# WallFollower-Circle.net
KiCad netlist of a schematic drawn in EAGLE
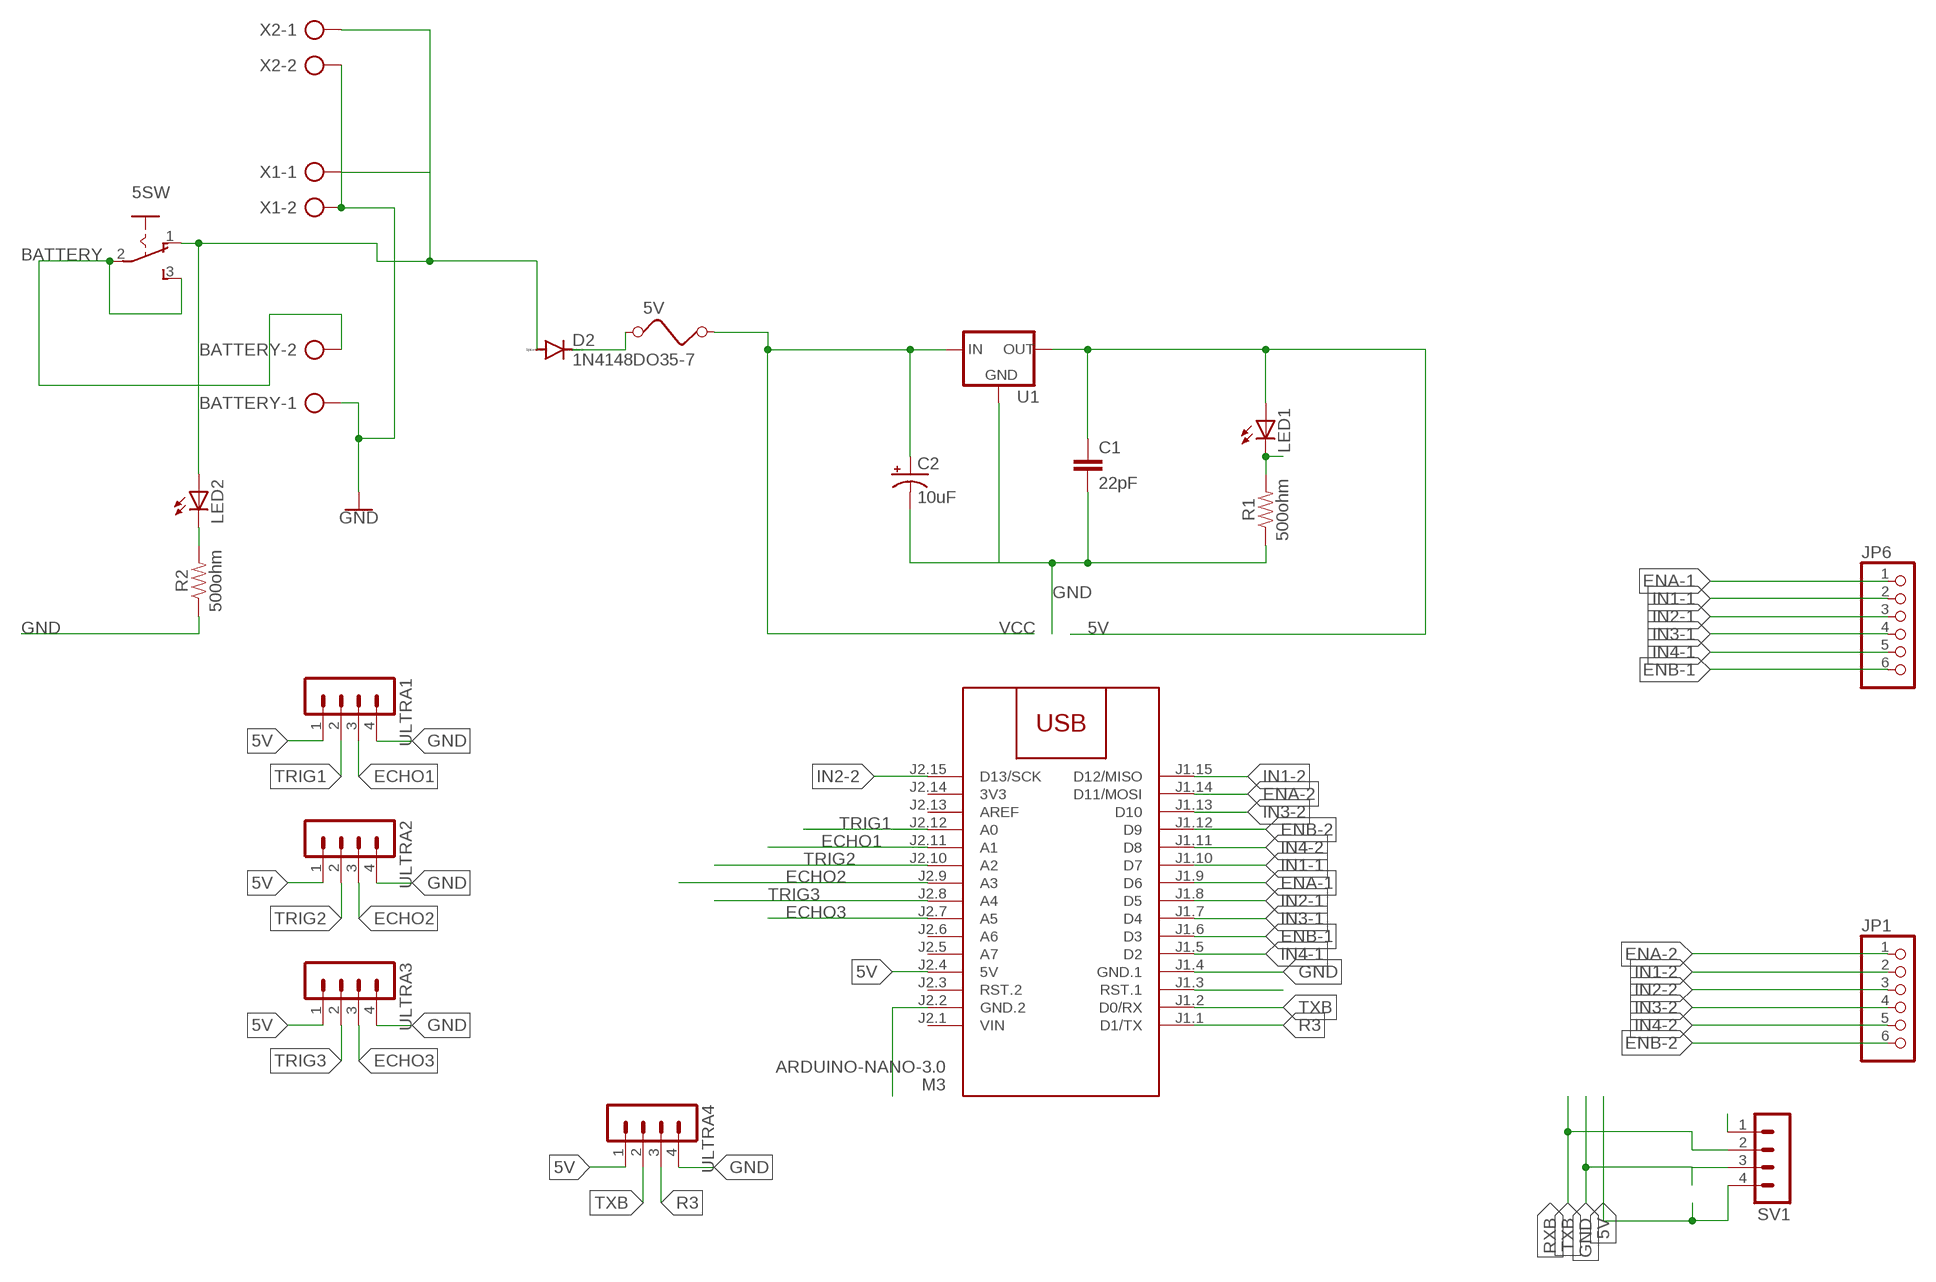
[diagram p0: schematic, sheet 1]

(export (version "E")
  (design (tool "Eeschema 10.0.6"))
  (components
    (comp (ref "5SW")
      (value "255SB")
      (footprint "eagle-import:255SB")
      (libsource (lib "eagle-import") (part "255SB"))
    )
    (comp (ref "5V")
      (value "FUSE")
      (footprint "eagle-import:FUSE")
      (libsource (lib "eagle-import") (part "FUSE"))
    )
    (comp (ref "BATTERY")
      (value "AK500/2-H")
      (footprint "eagle-import:AK500_2-H")
      (libsource (lib "eagle-import") (part "AK500/2-H"))
    )
    (comp (ref "C1")
      (value "22pF")
      (footprint "eagle-import:CAP-PTH-2.54")
      (libsource (lib "eagle-import") (part "22PF-PTH-2.54MM-200V-5%"))
    )
    (comp (ref "C2")
      (value "10uF")
      (footprint "eagle-import:CPOL-RADIAL-2.5MM-5MM")
      (libsource (lib "eagle-import") (part "10UF-POLAR-RADIAL-2.5MM-25V-20%"))
    )
    (comp (ref "D2")
      (value "1N4148DO35-7")
      (footprint "eagle-import:DO35-7")
      (libsource (lib "eagle-import") (part "1N4148DO35-7"))
    )
    (comp (ref "JP1")
      (value "PINHD-1X6")
      (footprint "eagle-import:1X06")
      (libsource (lib "eagle-import") (part "PINHD-1X6"))
    )
    (comp (ref "JP6")
      (value "PINHD-1X6")
      (footprint "eagle-import:1X06")
      (libsource (lib "eagle-import") (part "PINHD-1X6"))
    )
    (comp (ref "LED1")
      (value "LED3MM")
      (footprint "eagle-import:LED3MM")
      (libsource (lib "eagle-import") (part "LED3MM"))
    )
    (comp (ref "LED2")
      (value "LED3MM")
      (footprint "eagle-import:LED3MM")
      (libsource (lib "eagle-import") (part "LED3MM"))
    )
    (comp (ref "M3")
      (value "ARDUINO-NANO-3.0")
      (footprint "eagle-import:ARDUINO-NANO-3.0")
      (libsource (lib "eagle-import") (part "ARDUINO-NANO-3.0"))
    )
    (comp (ref "R1")
      (value "500ohm")
      (footprint "eagle-import:AXIAL-0.3")
      (libsource (lib "eagle-import") (part "10MOHM-HORIZ-1/4W-5%"))
    )
    (comp (ref "R2")
      (value "500ohm")
      (footprint "eagle-import:AXIAL-0.3")
      (libsource (lib "eagle-import") (part "10MOHM-HORIZ-1/4W-5%"))
    )
    (comp (ref "SV1")
      (value "MA04-1")
      (footprint "eagle-import:MA04-1")
      (libsource (lib "eagle-import") (part "MA04-1"))
    )
    (comp (ref "U1")
      (value "78XXS")
      (footprint "eagle-import:78XXS")
      (libsource (lib "eagle-import") (part "78XXS"))
    )
    (comp (ref "ULTRA1")
      (value "MA04-1")
      (footprint "eagle-import:MA04-1")
      (libsource (lib "eagle-import") (part "MA04-1"))
    )
    (comp (ref "ULTRA2")
      (value "MA04-1")
      (footprint "eagle-import:MA04-1")
      (libsource (lib "eagle-import") (part "MA04-1"))
    )
    (comp (ref "ULTRA3")
      (value "MA04-1")
      (footprint "eagle-import:MA04-1")
      (libsource (lib "eagle-import") (part "MA04-1"))
    )
    (comp (ref "ULTRA4")
      (value "MA04-1")
      (footprint "eagle-import:MA04-1")
      (libsource (lib "eagle-import") (part "MA04-1"))
    )
    (comp (ref "X1")
      (value "AK500/2-H")
      (footprint "eagle-import:AK500_2-H")
      (libsource (lib "eagle-import") (part "AK500/2-H"))
    )
    (comp (ref "X2")
      (value "AK500/2-H")
      (footprint "eagle-import:AK500_2-H")
      (libsource (lib "eagle-import") (part "AK500/2-H"))
    )
  )
  (nets
    (net (code "1") (name "/3V3") (class "Default")
      (node (ref "M3") (pin "J2.14") (pinfunction "3V3_J2.14") (pintype "power_in"))
    )
    (net (code "2") (name "/BATTERY") (class "Default")
      (node (ref "5SW") (pin "2") (pinfunction "P_2") (pintype "passive"))
      (node (ref "5SW") (pin "3") (pinfunction "S_3") (pintype "passive"))
      (node (ref "BATTERY") (pin "2") (pinfunction "KL_2") (pintype "passive"))
    )
    (net (code "3") (name "/VCC") (class "Default")
      (node (ref "5V") (pin "2") (pinfunction "2_2") (pintype "passive"))
      (node (ref "C2") (pin "1") (pinfunction "+_1") (pintype "passive"))
      (node (ref "U1") (pin "IN") (pinfunction "IN_IN") (pintype "input"))
    )
    (net (code "4") (name "/VIN") (class "Default")
      (node (ref "M3") (pin "J2.1") (pinfunction "VIN_J2.1") (pintype "power_in"))
    )
    (net (code "5") (name "5V") (class "Default")
      (node (ref "C1") (pin "1") (pinfunction "1_1") (pintype "passive"))
      (node (ref "LED1") (pin "A") (pinfunction "A_A") (pintype "passive"))
      (node (ref "M3") (pin "J2.4") (pinfunction "5V_J2.4") (pintype "power_in"))
      (node (ref "SV1") (pin "4") (pinfunction "4_4") (pintype "passive"))
      (node (ref "U1") (pin "OUT") (pinfunction "OUT_OUT") (pintype "passive"))
      (node (ref "ULTRA1") (pin "1") (pinfunction "1_1") (pintype "passive"))
      (node (ref "ULTRA2") (pin "1") (pinfunction "1_1") (pintype "passive"))
      (node (ref "ULTRA3") (pin "1") (pinfunction "1_1") (pintype "passive"))
      (node (ref "ULTRA4") (pin "1") (pinfunction "1_1") (pintype "passive"))
    )
    (net (code "6") (name "ECHO1") (class "Default")
      (node (ref "M3") (pin "J2.11") (pinfunction "A1_J2.11") (pintype "bidirectional"))
      (node (ref "ULTRA1") (pin "3") (pinfunction "3_3") (pintype "passive"))
    )
    (net (code "7") (name "ECHO2") (class "Default")
      (node (ref "M3") (pin "J2.9") (pinfunction "A3_J2.9") (pintype "bidirectional"))
      (node (ref "ULTRA2") (pin "3") (pinfunction "3_3") (pintype "passive"))
    )
    (net (code "8") (name "ECHO3") (class "Default")
      (node (ref "M3") (pin "J2.7") (pinfunction "A5_J2.7") (pintype "bidirectional"))
      (node (ref "ULTRA3") (pin "3") (pinfunction "3_3") (pintype "passive"))
    )
    (net (code "9") (name "ENA-1") (class "Default")
      (node (ref "JP6") (pin "1") (pinfunction "1_1") (pintype "passive"))
      (node (ref "M3") (pin "J1.9") (pinfunction "D6_J1.9") (pintype "bidirectional"))
    )
    (net (code "10") (name "ENA-2") (class "Default")
      (node (ref "JP1") (pin "1") (pinfunction "1_1") (pintype "passive"))
      (node (ref "M3") (pin "J1.14") (pinfunction "D11/MOSI_J1.14") (pintype "bidirectional"))
    )
    (net (code "11") (name "ENB-1") (class "Default")
      (node (ref "JP6") (pin "6") (pinfunction "6_6") (pintype "passive"))
      (node (ref "M3") (pin "J1.6") (pinfunction "D3_J1.6") (pintype "bidirectional"))
    )
    (net (code "12") (name "ENB-2") (class "Default")
      (node (ref "JP1") (pin "6") (pinfunction "6_6") (pintype "passive"))
      (node (ref "M3") (pin "J1.12") (pinfunction "D9_J1.12") (pintype "bidirectional"))
    )
    (net (code "13") (name "GND") (class "Default")
      (node (ref "BATTERY") (pin "1") (pinfunction "KL_1") (pintype "passive"))
      (node (ref "C1") (pin "2") (pinfunction "2_2") (pintype "passive"))
      (node (ref "C2") (pin "2") (pinfunction "-_2") (pintype "passive"))
      (node (ref "M3") (pin "J1.4") (pinfunction "GND.1_J1.4") (pintype "power_in"))
      (node (ref "M3") (pin "J2.2") (pinfunction "GND.2_J2.2") (pintype "power_in"))
      (node (ref "R1") (pin "P$1") (pinfunction "1_P$1") (pintype "passive"))
      (node (ref "R2") (pin "P$1") (pinfunction "1_P$1") (pintype "passive"))
      (node (ref "SV1") (pin "3") (pinfunction "3_3") (pintype "passive"))
      (node (ref "U1") (pin "GND") (pinfunction "GND_GND") (pintype "input"))
      (node (ref "ULTRA1") (pin "4") (pinfunction "4_4") (pintype "passive"))
      (node (ref "ULTRA2") (pin "4") (pinfunction "4_4") (pintype "passive"))
      (node (ref "ULTRA3") (pin "4") (pinfunction "4_4") (pintype "passive"))
      (node (ref "ULTRA4") (pin "4") (pinfunction "4_4") (pintype "passive"))
      (node (ref "X1") (pin "2") (pinfunction "KL_2") (pintype "passive"))
      (node (ref "X2") (pin "2") (pinfunction "KL_2") (pintype "passive"))
    )
    (net (code "14") (name "IN1-1") (class "Default")
      (node (ref "JP6") (pin "2") (pinfunction "2_2") (pintype "passive"))
      (node (ref "M3") (pin "J1.10") (pinfunction "D7_J1.10") (pintype "bidirectional"))
    )
    (net (code "15") (name "IN1-2") (class "Default")
      (node (ref "JP1") (pin "2") (pinfunction "2_2") (pintype "passive"))
      (node (ref "M3") (pin "J1.15") (pinfunction "D12/MISO_J1.15") (pintype "bidirectional"))
    )
    (net (code "16") (name "IN2-1") (class "Default")
      (node (ref "JP6") (pin "3") (pinfunction "3_3") (pintype "passive"))
      (node (ref "M3") (pin "J1.8") (pinfunction "D5_J1.8") (pintype "bidirectional"))
    )
    (net (code "17") (name "IN2-2") (class "Default")
      (node (ref "JP1") (pin "3") (pinfunction "3_3") (pintype "passive"))
      (node (ref "M3") (pin "J2.15") (pinfunction "D13/SCK_J2.15") (pintype "bidirectional"))
    )
    (net (code "18") (name "IN3-1") (class "Default")
      (node (ref "JP6") (pin "4") (pinfunction "4_4") (pintype "passive"))
      (node (ref "M3") (pin "J1.7") (pinfunction "D4_J1.7") (pintype "bidirectional"))
    )
    (net (code "19") (name "IN3-2") (class "Default")
      (node (ref "JP1") (pin "4") (pinfunction "4_4") (pintype "passive"))
      (node (ref "M3") (pin "J1.13") (pinfunction "D10_J1.13") (pintype "bidirectional"))
    )
    (net (code "20") (name "IN4-1") (class "Default")
      (node (ref "JP6") (pin "5") (pinfunction "5_5") (pintype "passive"))
      (node (ref "M3") (pin "J1.5") (pinfunction "D2_J1.5") (pintype "bidirectional"))
    )
    (net (code "21") (name "IN4-2") (class "Default")
      (node (ref "JP1") (pin "5") (pinfunction "5_5") (pintype "passive"))
      (node (ref "M3") (pin "J1.11") (pinfunction "D8_J1.11") (pintype "bidirectional"))
    )
    (net (code "22") (name "Net-(5SW-O)") (class "Default")
      (node (ref "5SW") (pin "1") (pinfunction "O_1") (pintype "passive"))
      (node (ref "D2") (pin "A") (pinfunction "A_A") (pintype "passive"))
      (node (ref "LED2") (pin "A") (pinfunction "A_A") (pintype "passive"))
      (node (ref "X1") (pin "1") (pinfunction "KL_1") (pintype "passive"))
      (node (ref "X2") (pin "1") (pinfunction "KL_1") (pintype "passive"))
    )
    (net (code "23") (name "Net-(5V-Pad1)") (class "Default")
      (node (ref "5V") (pin "1") (pinfunction "1_1") (pintype "passive"))
      (node (ref "D2") (pin "C") (pinfunction "C_C") (pintype "passive"))
    )
    (net (code "24") (name "Net-(LED1-C)") (class "Default")
      (node (ref "LED1") (pin "K") (pinfunction "C_K") (pintype "passive"))
      (node (ref "R1") (pin "P$2") (pinfunction "2_P$2") (pintype "passive"))
    )
    (net (code "25") (name "Net-(LED2-C)") (class "Default")
      (node (ref "LED2") (pin "K") (pinfunction "C_K") (pintype "passive"))
      (node (ref "R2") (pin "P$2") (pinfunction "2_P$2") (pintype "passive"))
    )
    (net (code "26") (name "R3") (class "Default")
      (node (ref "M3") (pin "J1.1") (pinfunction "D1/TX_J1.1") (pintype "bidirectional"))
      (node (ref "ULTRA4") (pin "3") (pinfunction "3_3") (pintype "passive"))
    )
    (net (code "27") (name "RXB") (class "Default")
      (node (ref "SV1") (pin "1") (pinfunction "1_1") (pintype "passive"))
    )
    (net (code "28") (name "TRIG1") (class "Default")
      (node (ref "M3") (pin "J2.12") (pinfunction "A0_J2.12") (pintype "bidirectional"))
      (node (ref "ULTRA1") (pin "2") (pinfunction "2_2") (pintype "passive"))
    )
    (net (code "29") (name "TRIG2") (class "Default")
      (node (ref "M3") (pin "J2.10") (pinfunction "A2_J2.10") (pintype "bidirectional"))
      (node (ref "ULTRA2") (pin "2") (pinfunction "2_2") (pintype "passive"))
    )
    (net (code "30") (name "TRIG3") (class "Default")
      (node (ref "M3") (pin "J2.8") (pinfunction "A4_J2.8") (pintype "bidirectional"))
      (node (ref "ULTRA3") (pin "2") (pinfunction "2_2") (pintype "passive"))
    )
    (net (code "31") (name "TXB") (class "Default")
      (node (ref "M3") (pin "J1.2") (pinfunction "D0/RX_J1.2") (pintype "bidirectional"))
      (node (ref "SV1") (pin "2") (pinfunction "2_2") (pintype "passive"))
      (node (ref "ULTRA4") (pin "2") (pinfunction "2_2") (pintype "passive"))
    )
    (net (code "32") (name "unconnected-(M3-A6-PadJ2.6)") (class "Default")
      (node (ref "M3") (pin "J2.6") (pinfunction "A6_J2.6") (pintype "bidirectional"))
    )
    (net (code "33") (name "unconnected-(M3-A7-PadJ2.5)") (class "Default")
      (node (ref "M3") (pin "J2.5") (pinfunction "A7_J2.5") (pintype "bidirectional"))
    )
    (net (code "34") (name "unconnected-(M3-AREF-PadJ2.13)") (class "Default")
      (node (ref "M3") (pin "J2.13") (pinfunction "AREF_J2.13") (pintype "bidirectional"))
    )
    (net (code "35") (name "unconnected-(M3-RST.1-PadJ1.3)") (class "Default")
      (node (ref "M3") (pin "J1.3") (pinfunction "RST.1_J1.3") (pintype "bidirectional"))
    )
    (net (code "36") (name "unconnected-(M3-RST.2-PadJ2.3)") (class "Default")
      (node (ref "M3") (pin "J2.3") (pinfunction "RST.2_J2.3") (pintype "bidirectional"))
    )
  )
)
